# 3_3V_DIST.net
KiCad netlist of a schematic drawn in Altium Designer
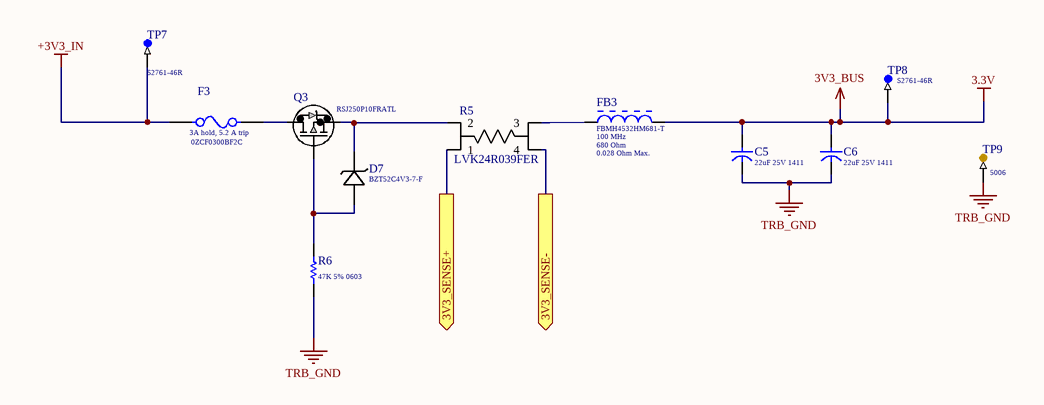
[diagram p0: 3_3V_DIST.SchDoc]

(export (version "E")
  (design (tool "Eeschema 10.0.6"))
  (components
    (comp (ref "C5")
      (value "Cap_Kemet_T521B226M025ATE100_22uF")
      (footprint "Cap_Kemet_T521B226M025ATE100_22uF")
      (description "Tantalum Capacitors - Polymer SMD 25V 22uF 1311 20% ESR=100mOhms")
      (fields (field (name "CAPACITANCE") "22uF 25V 1411"))
      (libsource (lib "Cap_Kemet_T521B226M025ATE100_22uF") (part "Cap_Kemet_T521B226M025ATE100_22uF"))
    )
    (comp (ref "C6")
      (value "Cap_Kemet_T521B226M025ATE100_22uF")
      (footprint "Cap_Kemet_T521B226M025ATE100_22uF")
      (description "Tantalum Capacitors - Polymer SMD 25V 22uF 1311 20% ESR=100mOhms")
      (fields (field (name "CAPACITANCE") "22uF 25V 1411"))
      (libsource (lib "Cap_Kemet_T521B226M025ATE100_22uF") (part "Cap_Kemet_T521B226M025ATE100_22uF"))
    )
    (comp (ref "D7")
      (value "BZT52C4V3-7-F")
      (footprint "SOD123")
      (description "Zener Diodes 500mW 4.3V Zener AEC-Q101 Qualified")
      (fields (field (name "SERIES") "BZT52C4V3-7-F"))
      (libsource (lib "4v3_zener_BZT52C4V3-7-F") (part "BZT52C4V3-7-F"))
    )
    (comp (ref "F3")
      (value "3A hold, 5.2 A trip")
      (footprint "Bel_0ZCF_MFG")
      (description "Resettable Fuses - PPTC 3A 24V PPTC 2920 SMD")
      (fields (field (name "SERIES") "0ZCF0300BF2C"))
      (libsource (lib "Fuse_Bel_0ZCF0300BF2C_3A_hold") (part "0ZCF0300BF2C"))
    )
    (comp (ref "FB3")
      (value "FBMH4532HM681-T")
      (footprint "TAYO-FBMH4532-2_V")
      (fields
        (field (name "PARTNUMBER") "FBMH4532HM681-T")
        (field (name "MANUFACTURER") "Taiyo Yuden")
        (field (name "MEASURING FREQUENCY") "100 MHz")
        (field (name "NOMINAL IMPEDANCE") "680 Ohm")
        (field (name "DC RESISTANCE") "0.028 Ohm Max.")
      )
      (libsource (lib "Taiyo_Yuden_FBMH4532HM681") (part "FBMH4532HM681-T"))
    )
    (comp (ref "Q3")
      (value "Mos_ROHM_RSJ250P10FRATL_25A")
      (footprint "Mos_ROHM_RSJ250P10FRATL_25A")
      (description "MOSFET Pch -100V Vds -25A 0.05Rds(on) 60Qg")
      (fields (field (name "SERIES") "RSJ250P10FRATL"))
      (libsource (lib "Mos_ROHM_RSJ250P10FRATL_25A") (part "Mos_ROHM_RSJ250P10FRATL_25A"))
    )
    (comp (ref "R5")
      (value "LVK24R039FER")
      (footprint "OH_LVK24_OHM")
      (description "RES 0.039 OHM 1% 1W 2412")
      (fields (field (name "COPYRIGHT") "Copyright (C) 2018 Accelerated Designs. All rights reserved"))
      (libsource (lib "Shunt_Res_Ohmite_LVK24R039FER") (part "LVK24R039FER"))
    )
    (comp (ref "R6")
      (value "47K 5% 0603")
      (footprint "RESC0603(1608)_L")
      (description "47K 0.1W 5% 0603 (1608 Metric)  SMD")
      (fields (field (name "TOLERANCE") "5 %") (field (name "POWER") "0.1 W"))
      (libsource (lib "Altium Content Vault") (part "RES"))
    )
    (comp (ref "TP7")
      (value "TP_Harwin_S2761_46R")
      (footprint "TP_Harwin_S2761_46R")
      (description "Circuit Board Hardware - PCB SMT Mini Test Terminal, Reel")
      (fields (field (name "SERIES") "S2761-46R"))
      (libsource (lib "TP_Harwin_S2761_46R") (part "TP_Harwin_S2761_46R"))
    )
    (comp (ref "TP8")
      (value "TP_Harwin_S2761_46R")
      (footprint "TP_Harwin_S2761_46R")
      (description "Circuit Board Hardware - PCB SMT Mini Test Terminal, Reel")
      (fields (field (name "SERIES") "S2761-46R"))
      (libsource (lib "TP_Harwin_S2761_46R") (part "TP_Harwin_S2761_46R"))
    )
    (comp (ref "TP9")
      (value "TP_Keystone_Electronics_5006")
      (footprint "TP_Keystone_Electronics_5006")
      (description "Circuit Board Hardware - PCB TEST POINT BLK .063")
      (fields (field (name "SERIES") "5006"))
      (libsource (lib "TP_Keystone_Electronics_5006") (part "TP_Keystone_Electronics_5006"))
    )
  )
  (nets
    (net (code "1") (name "+3V3_IN") (class "Default")
      (node (ref "F3") (pin "1") (pinfunction "1_1") (pintype "passive"))
      (node (ref "TP7") (pin "1") (pinfunction "1_1") (pintype "input"))
    )
    (net (code "2") (name "/3V3_SENSE+") (class "Default")
      (node (ref "R5") (pin "1") (pinfunction "1_1") (pintype "passive"))
    )
    (net (code "3") (name "/3V3_SENSE-") (class "Default")
      (node (ref "R5") (pin "4") (pinfunction "4_4") (pintype "passive"))
    )
    (net (code "4") (name "3.3V") (class "Default")
      (node (ref "C5") (pin "1") (pinfunction "1_1") (pintype "passive"))
      (node (ref "C6") (pin "1") (pinfunction "1_1") (pintype "passive"))
      (node (ref "FB3") (pin "2") (pinfunction "2_2") (pintype "passive"))
      (node (ref "TP8") (pin "1") (pinfunction "1_1") (pintype "input"))
    )
    (net (code "5") (name "Net-(FB3-Pad1)") (class "Default")
      (node (ref "FB3") (pin "1") (pinfunction "1_1") (pintype "passive"))
      (node (ref "R5") (pin "3") (pinfunction "3_3") (pintype "passive"))
    )
    (net (code "6") (name "Net-(Q3-D)") (class "Default")
      (node (ref "F3") (pin "2") (pinfunction "2_2") (pintype "passive"))
      (node (ref "Q3") (pin "2") (pinfunction "D_2") (pintype "passive"))
    )
    (net (code "7") (name "Net-(Q3-G)") (class "Default")
      (node (ref "D7") (pin "2") (pinfunction "2_2") (pintype "passive"))
      (node (ref "Q3") (pin "1") (pinfunction "G_1") (pintype "passive"))
      (node (ref "R6") (pin "2") (pinfunction "2_2") (pintype "passive"))
    )
    (net (code "8") (name "Net-(Q3-S)") (class "Default")
      (node (ref "D7") (pin "1") (pinfunction "1_1") (pintype "passive"))
      (node (ref "Q3") (pin "3") (pinfunction "S_3") (pintype "passive"))
      (node (ref "R5") (pin "2") (pinfunction "2_2") (pintype "passive"))
    )
    (net (code "9") (name "TRB_GND") (class "Default")
      (node (ref "C5") (pin "2") (pinfunction "2_2") (pintype "passive"))
      (node (ref "C6") (pin "2") (pinfunction "2_2") (pintype "passive"))
      (node (ref "R6") (pin "1") (pinfunction "1_1") (pintype "passive"))
      (node (ref "TP9") (pin "1") (pinfunction "1_1") (pintype "input"))
    )
  )
)
